# Board-DCDC.net
KiCad netlist of a schematic drawn in Altium Designer
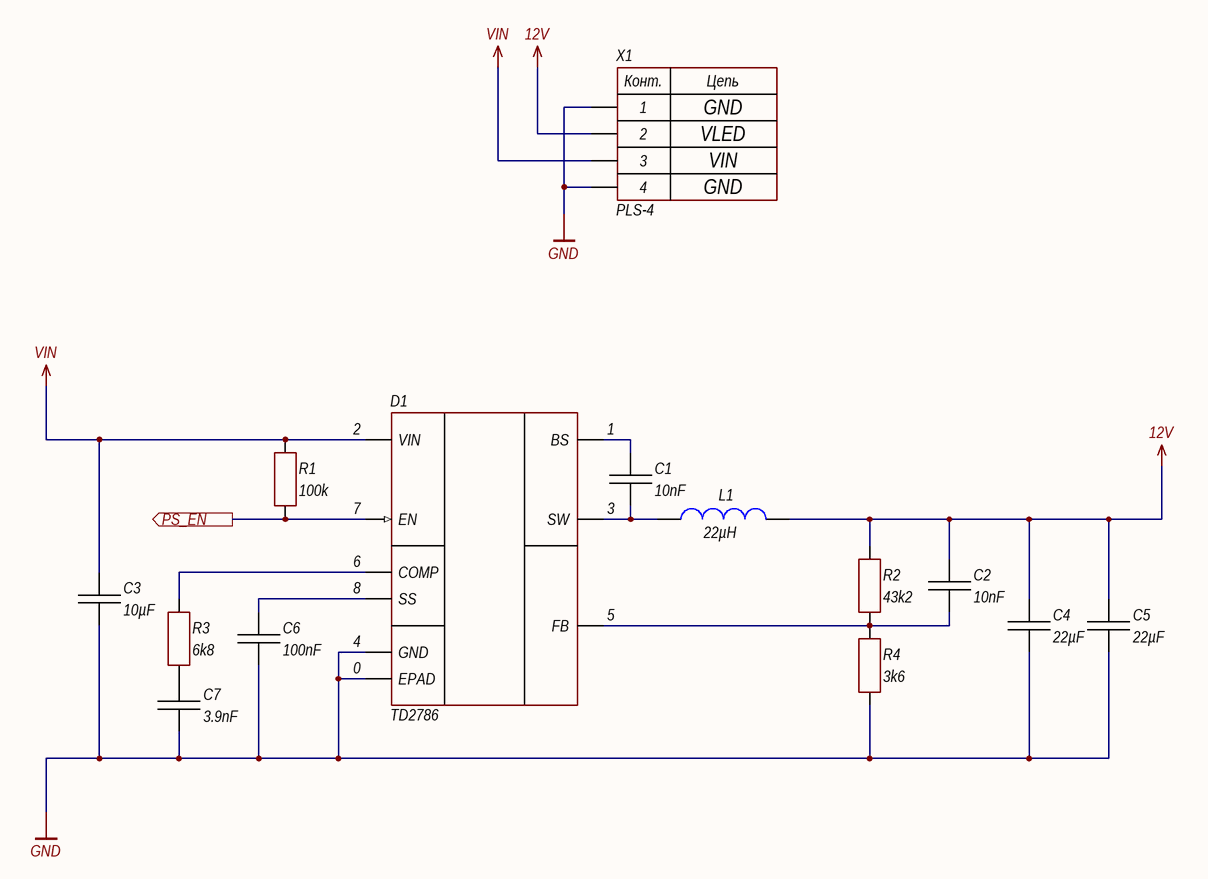
[diagram p0: Board-DCDC.SchDoc]

(export (version "E")
  (design (tool "Eeschema 10.0.6"))
  (components
    (comp (ref "C1")
      (value "10nF")
      (footprint "CH0402C")
      (fields (field (name "MANUFACTURER") "CCTC"))
      (libsource (lib "Discrete") (part "Capacitor"))
    )
    (comp (ref "C2")
      (value "10nF")
      (footprint "CH0402C")
      (fields (field (name "MANUFACTURER") "CCTC"))
      (libsource (lib "Discrete") (part "Capacitor"))
    )
    (comp (ref "C3")
      (value "10µF")
      (footprint "standard:CH1210C")
      (fields (field (name "MANUFACTURER") "Murata Electronics"))
      (libsource (lib "Discrete") (part "Capacitor"))
    )
    (comp (ref "C4")
      (value "22µF")
      (footprint "standard:CH1210C")
      (fields (field (name "MANUFACTURER") "Murata Electronics"))
      (libsource (lib "Discrete") (part "Capacitor"))
    )
    (comp (ref "C5")
      (value "22µF")
      (footprint "standard:CH1210C")
      (fields (field (name "MANUFACTURER") "Murata Electronics"))
      (libsource (lib "Discrete") (part "Capacitor"))
    )
    (comp (ref "C6")
      (value "100nF")
      (footprint "CH0402C")
      (fields (field (name "MANUFACTURER") "CCTC"))
      (libsource (lib "Discrete") (part "Capacitor"))
    )
    (comp (ref "C7")
      (value "3.9nF")
      (footprint "CH0402C")
      (fields (field (name "MANUFACTURER") "YAGEO"))
      (libsource (lib "Discrete") (part "Capacitor"))
    )
    (comp (ref "D1")
      (value "TD2786")
      (footprint "8-SOIC (PAD)")
      (description "Step-down")
      (fields (field (name "MANUFACTURER") "Techcode Semiconductor Limited"))
      (libsource (lib "Power Supplies") (part "TD2786"))
    )
    (comp (ref "L1")
      (value "22µH")
      (footprint "IND: JSHC1040")
      (fields (field (name "MANUFACTURER") "Jinlai"))
      (libsource (lib "Discrete") (part "Inductor"))
    )
    (comp (ref "R1")
      (value "100k")
      (footprint "CH0402R")
      (fields (field (name "MANUFACTURER") "Uniroyal Elec"))
      (libsource (lib "Discrete") (part "Resistor"))
    )
    (comp (ref "R2")
      (value "43k2")
      (footprint "CH0402R")
      (fields (field (name "MANUFACTURER") "YAGEO"))
      (libsource (lib "Discrete") (part "Resistor"))
    )
    (comp (ref "R3")
      (value "6k8")
      (footprint "CH0402R")
      (fields (field (name "MANUFACTURER") "Uniroyal Elec"))
      (libsource (lib "Discrete") (part "Resistor"))
    )
    (comp (ref "R4")
      (value "3k6")
      (footprint "CH0402R")
      (fields (field (name "MANUFACTURER") "YAGEO"))
      (libsource (lib "Discrete") (part "Resistor"))
    )
    (comp (ref "X1")
      (value "PLS-4")
      (footprint "CON: PLS-4")
      (libsource (lib "Connectors") (part "4-Connector"))
    )
  )
  (nets
    (net (code "1") (name "/PS_EN") (class "Default")
      (node (ref "D1") (pin "7") (pinfunction "EN_7") (pintype "input"))
      (node (ref "R1") (pin "1") (pinfunction "1_1") (pintype "passive"))
    )
    (net (code "2") (name "12V") (class "Default")
      (node (ref "C2") (pin "2") (pinfunction "2_2") (pintype "power_in"))
      (node (ref "C4") (pin "2") (pinfunction "2_2") (pintype "power_in"))
      (node (ref "C5") (pin "2") (pinfunction "2_2") (pintype "power_in"))
      (node (ref "L1") (pin "1") (pinfunction "1_1") (pintype "passive"))
      (node (ref "R2") (pin "2") (pinfunction "2_2") (pintype "passive"))
      (node (ref "X1") (pin "2") (pinfunction "2_2") (pintype "passive"))
    )
    (net (code "3") (name "GND") (class "Default")
      (node (ref "C3") (pin "1") (pinfunction "1_1") (pintype "power_in"))
      (node (ref "C4") (pin "1") (pinfunction "1_1") (pintype "power_in"))
      (node (ref "C5") (pin "1") (pinfunction "1_1") (pintype "power_in"))
      (node (ref "C6") (pin "1") (pinfunction "1_1") (pintype "power_in"))
      (node (ref "C7") (pin "1") (pinfunction "1_1") (pintype "power_in"))
      (node (ref "D1") (pin "0") (pinfunction "EPAD_0") (pintype "power_in"))
      (node (ref "D1") (pin "4") (pinfunction "GND_4") (pintype "power_in"))
      (node (ref "R4") (pin "1") (pinfunction "1_1") (pintype "passive"))
      (node (ref "X1") (pin "1") (pinfunction "1_1") (pintype "passive"))
      (node (ref "X1") (pin "4") (pinfunction "4_4") (pintype "passive"))
    )
    (net (code "4") (name "Net-(C7-Pad2)") (class "Default")
      (node (ref "C7") (pin "2") (pinfunction "2_2") (pintype "power_in"))
      (node (ref "R3") (pin "1") (pinfunction "1_1") (pintype "passive"))
    )
    (net (code "5") (name "Net-(D1-BS)") (class "Default")
      (node (ref "C1") (pin "2") (pinfunction "2_2") (pintype "power_in"))
      (node (ref "D1") (pin "1") (pinfunction "BS_1") (pintype "power_in"))
    )
    (net (code "6") (name "Net-(D1-COMP)") (class "Default")
      (node (ref "D1") (pin "6") (pinfunction "COMP_6") (pintype "power_in"))
      (node (ref "R3") (pin "2") (pinfunction "2_2") (pintype "passive"))
    )
    (net (code "7") (name "Net-(D1-FB)") (class "Default")
      (node (ref "C2") (pin "1") (pinfunction "1_1") (pintype "power_in"))
      (node (ref "D1") (pin "5") (pinfunction "FB_5") (pintype "power_in"))
      (node (ref "R2") (pin "1") (pinfunction "1_1") (pintype "passive"))
      (node (ref "R4") (pin "2") (pinfunction "2_2") (pintype "passive"))
    )
    (net (code "8") (name "Net-(D1-SS)") (class "Default")
      (node (ref "C6") (pin "2") (pinfunction "2_2") (pintype "power_in"))
      (node (ref "D1") (pin "8") (pinfunction "SS_8") (pintype "power_in"))
    )
    (net (code "9") (name "Net-(D1-SW)") (class "Default")
      (node (ref "C1") (pin "1") (pinfunction "1_1") (pintype "power_in"))
      (node (ref "D1") (pin "3") (pinfunction "SW_3") (pintype "power_in"))
      (node (ref "L1") (pin "2") (pinfunction "2_2") (pintype "passive"))
    )
    (net (code "10") (name "VIN") (class "Default")
      (node (ref "C3") (pin "2") (pinfunction "2_2") (pintype "power_in"))
      (node (ref "D1") (pin "2") (pinfunction "VIN_2") (pintype "power_in"))
      (node (ref "R1") (pin "2") (pinfunction "2_2") (pintype "passive"))
      (node (ref "X1") (pin "3") (pinfunction "3_3") (pintype "passive"))
    )
  )
)
